# NVME.net
KiCad netlist of a schematic drawn in Altium Designer
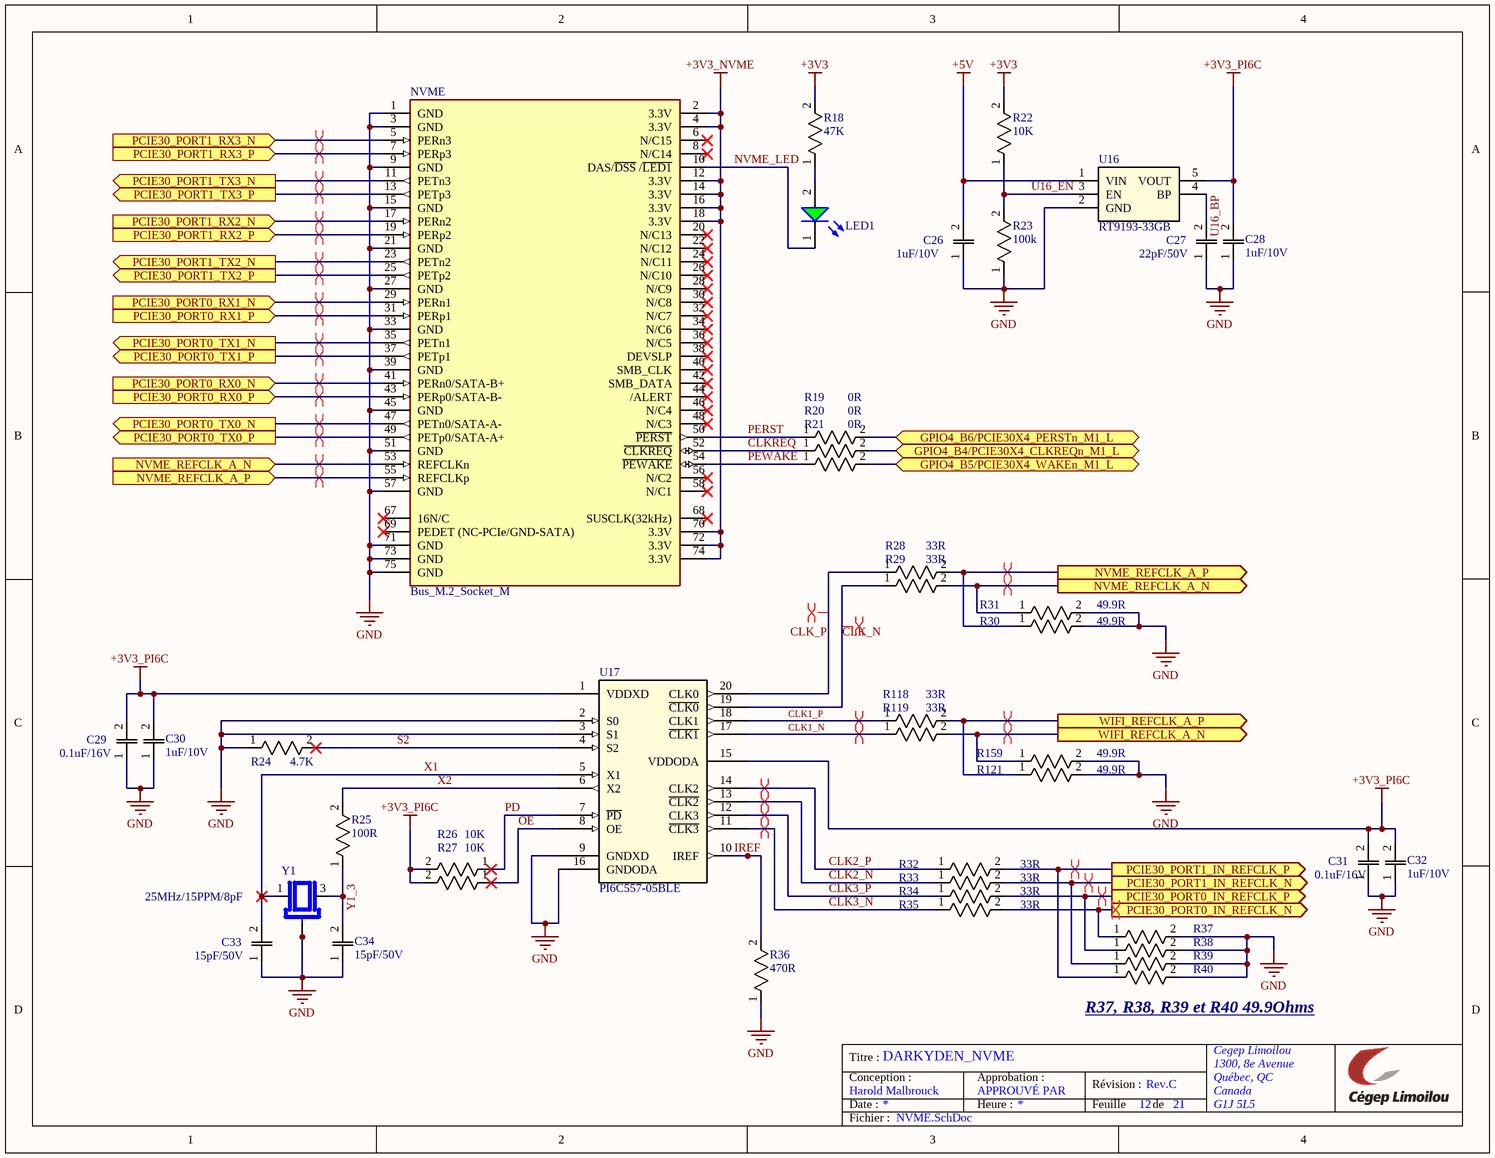
[diagram p0: NVME.SchDoc]

(export (version "E")
  (design (tool "Eeschema 10.0.6"))
  (components
    (comp (ref "C26")
      (value "1uF/10V")
      (footprint "C0805")
      (description "Multilayer Ceramic Capacitors MLCC - SMD/SMT 10V 1uF X7R 0805 10%")
      (fields
        (field (name "MANUFACTURER") "KEMET")
        (field (name "MANUFACTURER PART NUMBER") "C0805C105K3RACTU")
      )
      (libsource (lib "DARKYDEN") (part "C0805C105K8RACTU"))
    )
    (comp (ref "C27")
      (value "22pF/50V")
      (footprint "C0805")
      (description "Cap Ceramic 22pF 50V X7R 5% Pad SMD 0805 125°C T/R")
      (fields
        (field (name "MANUFACTURER") "KEMET")
        (field (name "MANUFACTURER PART NUMBER") "C0805C220J5RACTU")
      )
      (libsource (lib "DARKYDEN") (part "C0805C220J5RACTU"))
    )
    (comp (ref "C28")
      (value "1uF/10V")
      (footprint "C0805")
      (description "Multilayer Ceramic Capacitors MLCC - SMD/SMT 10V 1uF X7R 0805 10%")
      (fields
        (field (name "MANUFACTURER") "KEMET")
        (field (name "MANUFACTURER PART NUMBER") "C0805C105K3RACTU")
      )
      (libsource (lib "DARKYDEN") (part "C0805C105K8RACTU"))
    )
    (comp (ref "C29")
      (value "0.1uF/16V")
      (footprint "C0805")
      (description "0.1uF/16V ±10% X7R 0805 (2012METRIC) Ceramic Capacitor SMD Auto X7R")
      (fields
        (field (name "MANUFACTURER") "KEMET")
        (field (name "MANUFACTURER PART NUMBER") "C0805C104K5RACTU")
      )
      (libsource (lib "DARKYDEN") (part "C0805C104K4RACAUTO"))
    )
    (comp (ref "C30")
      (value "1uF/10V")
      (footprint "C0805")
      (description "Multilayer Ceramic Capacitors MLCC - SMD/SMT 10V 1uF X7R 0805 10%")
      (fields
        (field (name "MANUFACTURER") "KEMET")
        (field (name "MANUFACTURER PART NUMBER") "C0805C105K3RACTU")
      )
      (libsource (lib "DARKYDEN") (part "C0805C105K8RACTU"))
    )
    (comp (ref "C31")
      (value "0.1uF/16V")
      (footprint "C0805")
      (description "0.1uF/16V ±10% X7R 0805 (2012METRIC) Ceramic Capacitor SMD Auto X7R")
      (fields
        (field (name "MANUFACTURER") "KEMET")
        (field (name "MANUFACTURER PART NUMBER") "C0805C104K5RACTU")
      )
      (libsource (lib "DARKYDEN") (part "C0805C104K4RACAUTO"))
    )
    (comp (ref "C32")
      (value "1uF/10V")
      (footprint "C0805")
      (description "Multilayer Ceramic Capacitors MLCC - SMD/SMT 10V 1uF X7R 0805 10%")
      (fields
        (field (name "MANUFACTURER") "KEMET")
        (field (name "MANUFACTURER PART NUMBER") "C0805C105K3RACTU")
      )
      (libsource (lib "DARKYDEN") (part "C0805C105K8RACTU"))
    )
    (comp (ref "C33")
      (value "15pF/50V")
      (footprint "C0805")
      (description "Multilayer Ceramic Capacitors MLCC - SMD/SMT 50V 15pF X7R 0805 10% AEC-Q200")
      (fields
        (field (name "MANUFACTURER") "KEMET")
        (field (name "MANUFACTURER PART NUMBER") "C0805C150K5RACAUTO")
      )
      (libsource (lib "DARKYDEN") (part "C0805C150K5RACAUTO"))
    )
    (comp (ref "C34")
      (value "15pF/50V")
      (footprint "C0805")
      (description "Multilayer Ceramic Capacitors MLCC - SMD/SMT 50V 15pF X7R 0805 10% AEC-Q200")
      (fields
        (field (name "MANUFACTURER") "KEMET")
        (field (name "MANUFACTURER PART NUMBER") "C0805C150K5RACAUTO")
      )
      (libsource (lib "DARKYDEN") (part "C0805C150K5RACAUTO"))
    )
    (comp (ref "LED1")
      (value "Green, 3.2V, 140°")
      (footprint "WL-SMCD_0603")
      (description "WL-SMCD Mono-color Chip LED Diffused, SMT, size 0603, Green, 3.2V, 140°")
      (fields
        (field (name "MANUFACTURER PART NUMBER") "150060GS55040")
        (field (name "MANUFACTURER") "Wurth Elektronik")
      )
      (libsource (lib "0603_LED") (part "GREEN"))
    )
    (comp (ref "NVME")
      (value "Bus_M.2_Socket_M")
      (footprint "AMPHENOL_MDT420M03001")
      (fields
        (field (name "MF") "Amphenol Commercial")
        (field (name "MANUFACTURER PART NUMBER") "MDT420M03001")
      )
      (libsource (lib "Bus_M.2_Socket_M") (part "Bus_M.2_Socket_M"))
    )
    (comp (ref "R18")
      (value "47K")
      (footprint "RESC1608X55N")
      (description "47K Ohm 5% 1/10W 0603 200ppm/C Molded SMD Punched Carrier T/R")
      (fields
        (field (name "MANUFACTURER") "Panasonic")
        (field (name "MANUFACTURER PART NUMBER") "ERJ-3GEYJ473V")
      )
      (libsource (lib "DARKYDEN") (part "ERJ-3GEYJ473V"))
    )
    (comp (ref "R19")
      (value "0R")
      (footprint "SamacSys:RESC1608X55N")
      (description "Zero Ohm Resistor, Jumper, 0603 [1608 Metric], Thick Film, 100 mW, 1 A, Surface Mount")
      (fields
        (field (name "MOUSER PART NUMBER") "667-ERJ-3GEY0R00V")
        (field (name "ARROW PART NUMBER") "ERJ-3GEY0R00V")
      )
      (libsource (lib "DARKYDEN") (part "ERJ-3GEY0R00V"))
    )
    (comp (ref "R20")
      (value "0R")
      (footprint "SamacSys:RESC1608X55N")
      (description "Zero Ohm Resistor, Jumper, 0603 [1608 Metric], Thick Film, 100 mW, 1 A, Surface Mount")
      (fields
        (field (name "MOUSER PART NUMBER") "667-ERJ-3GEY0R00V")
        (field (name "ARROW PART NUMBER") "ERJ-3GEY0R00V")
      )
      (libsource (lib "DARKYDEN") (part "ERJ-3GEY0R00V"))
    )
    (comp (ref "R21")
      (value "0R")
      (footprint "SamacSys:RESC1608X55N")
      (description "Zero Ohm Resistor, Jumper, 0603 [1608 Metric], Thick Film, 100 mW, 1 A, Surface Mount")
      (fields
        (field (name "MOUSER PART NUMBER") "667-ERJ-3GEY0R00V")
        (field (name "ARROW PART NUMBER") "ERJ-3GEY0R00V")
      )
      (libsource (lib "DARKYDEN") (part "ERJ-3GEY0R00V"))
    )
    (comp (ref "R22")
      (value "10K")
      (footprint "SamacSys:RESC1608X55N")
      (description "10K Ohm 5% Res Thick Film 0603  0.1W(1/10W) ±200ppm/C Pad SMD Automotive T/R")
      (fields
        (field (name "MOUSER PART NUMBER") "667-ERJ-3GEYJ103V")
        (field (name "ARROW PART NUMBER") "ERJ-3GEYJ103V")
      )
      (libsource (lib "DARKYDEN") (part "ERJ-3GEYJ103V"))
    )
    (comp (ref "R23")
      (value "100k")
      (footprint "SamacSys:RESC1608X55N")
      (description "100K Ohm 5%  Res Thick Film 0603 1/10W +/-200ppm/ßC Molded SMD Punched Carrier T/R")
      (fields
        (field (name "MOUSER PART NUMBER") "667-ERJ-3GEYJ104V")
        (field (name "ARROW PART NUMBER") "ERJ-3GEYJ104V")
      )
      (libsource (lib "DARKYDEN") (part "ERJ-3GEYJ104V"))
    )
    (comp (ref "R24")
      (value "4.7K")
      (footprint "RESC1608X55N")
      (description "4.7K Ohm 0.1% 0.1W 0603 ±25ppm/°C Molded SMD Punched Carrier T/R")
      (fields
        (field (name "MANUFACTURER") "Panasonic")
        (field (name "MANUFACTURER PART NUMBER") "ERA-3AEB472V")
      )
      (libsource (lib "DARKYDEN") (part "ERA-3AEB472V"))
    )
    (comp (ref "R25")
      (value "100R")
      (footprint "SamacSys:RESC1608X55N")
      (description "100 Ohm 1% 1/10W 0603 ±100ppm/°C Molded SMD Punched Carrier T/R")
      (fields
        (field (name "MOUSER PART NUMBER") "667-ERJ-3EKF1000V")
        (field (name "ARROW PART NUMBER") "ERJ-3EKF1000V")
      )
      (libsource (lib "DARKYDEN") (part "ERJ-3EKF1000V"))
    )
    (comp (ref "R26")
      (value "10K")
      (footprint "SamacSys:RESC1608X55N")
      (description "10K Ohm 5% Res Thick Film 0603  0.1W(1/10W) ±200ppm/C Pad SMD Automotive T/R")
      (fields
        (field (name "MOUSER PART NUMBER") "667-ERJ-3GEYJ103V")
        (field (name "ARROW PART NUMBER") "ERJ-3GEYJ103V")
      )
      (libsource (lib "DARKYDEN") (part "ERJ-3GEYJ103V"))
    )
    (comp (ref "R27")
      (value "10K")
      (footprint "SamacSys:RESC1608X55N")
      (description "10K Ohm 5% Res Thick Film 0603  0.1W(1/10W) ±200ppm/C Pad SMD Automotive T/R")
      (fields
        (field (name "MOUSER PART NUMBER") "667-ERJ-3GEYJ103V")
        (field (name "ARROW PART NUMBER") "ERJ-3GEYJ103V")
      )
      (libsource (lib "DARKYDEN") (part "ERJ-3GEYJ103V"))
    )
    (comp (ref "R28")
      (value "33R")
      (footprint "RESC1608X55N")
      (description "33 Ohm 1% 0.1W 0603 ±100ppm/°C Molded SMD Punched Carrier T/R")
      (fields
        (field (name "MANUFACTURER") "Panasonic")
        (field (name "MANUFACTURER PART NUMBER") "ERJ-3EKF33R0V")
      )
      (libsource (lib "DARKYDEN") (part "ERJ-3EKF33R0V"))
    )
    (comp (ref "R29")
      (value "33R")
      (footprint "RESC1608X55N")
      (description "33 Ohm 1% 0.1W 0603 ±100ppm/°C Molded SMD Punched Carrier T/R")
      (fields
        (field (name "MANUFACTURER") "Panasonic")
        (field (name "MANUFACTURER PART NUMBER") "ERJ-3EKF33R0V")
      )
      (libsource (lib "DARKYDEN") (part "ERJ-3EKF33R0V"))
    )
    (comp (ref "R30")
      (value "49.9R")
      (footprint "RESC1608X55N")
      (description "100Mw Thick Film Resistors 100Ppm/ 1% 49.9 0603 Chip Resistor Surface Mount Rohs")
      (fields
        (field (name "MANUFACTURER") "Panasonic")
        (field (name "MANUFACTURER PART NUMBER") "ERJ-3EKF49R9V")
      )
      (libsource (lib "DARKYDEN") (part "ERJ-3EKF49R9V"))
    )
    (comp (ref "R31")
      (value "49.9R")
      (footprint "RESC1608X55N")
      (description "100Mw Thick Film Resistors 100Ppm/ 1% 49.9 0603 Chip Resistor Surface Mount Rohs")
      (fields
        (field (name "MANUFACTURER") "Panasonic")
        (field (name "MANUFACTURER PART NUMBER") "ERJ-3EKF49R9V")
      )
      (libsource (lib "DARKYDEN") (part "ERJ-3EKF49R9V"))
    )
    (comp (ref "R32")
      (value "33R")
      (footprint "RESC1608X55N")
      (description "33 Ohm 1% 0.1W 0603 ±100ppm/°C Molded SMD Punched Carrier T/R")
      (fields
        (field (name "MANUFACTURER") "Panasonic")
        (field (name "MANUFACTURER PART NUMBER") "ERJ-3EKF33R0V")
      )
      (libsource (lib "DARKYDEN") (part "ERJ-3EKF33R0V"))
    )
    (comp (ref "R33")
      (value "33R")
      (footprint "RESC1608X55N")
      (description "33 Ohm 1% 0.1W 0603 ±100ppm/°C Molded SMD Punched Carrier T/R")
      (fields
        (field (name "MANUFACTURER") "Panasonic")
        (field (name "MANUFACTURER PART NUMBER") "ERJ-3EKF33R0V")
      )
      (libsource (lib "DARKYDEN") (part "ERJ-3EKF33R0V"))
    )
    (comp (ref "R34")
      (value "33R")
      (footprint "RESC1608X55N")
      (description "33 Ohm 1% 0.1W 0603 ±100ppm/°C Molded SMD Punched Carrier T/R")
      (fields
        (field (name "MANUFACTURER") "Panasonic")
        (field (name "MANUFACTURER PART NUMBER") "ERJ-3EKF33R0V")
      )
      (libsource (lib "DARKYDEN") (part "ERJ-3EKF33R0V"))
    )
    (comp (ref "R35")
      (value "33R")
      (footprint "RESC1608X55N")
      (description "33 Ohm 1% 0.1W 0603 ±100ppm/°C Molded SMD Punched Carrier T/R")
      (fields
        (field (name "MANUFACTURER") "Panasonic")
        (field (name "MANUFACTURER PART NUMBER") "ERJ-3EKF33R0V")
      )
      (libsource (lib "DARKYDEN") (part "ERJ-3EKF33R0V"))
    )
    (comp (ref "R36")
      (value "470R")
      (footprint "RESC1608X55N")
      (description "470 Ohm 5% 1/10W 0603 +/-200ppm/ßC Molded SMD Punched Carrier T/R")
      (fields
        (field (name "MANUFACTURER") "Panasonic")
        (field (name "MANUFACTURER PART NUMBER") "ERJ-3GEYJ471V")
      )
      (libsource (lib "DARKYDEN") (part "ERJ-3GEYJ471V"))
    )
    (comp (ref "R37")
      (value "49.9R")
      (footprint "RESC1608X55N")
      (description "100Mw Thick Film Resistors 100Ppm/ 1% 49.9 0603 Chip Resistor Surface Mount Rohs")
      (fields
        (field (name "MANUFACTURER") "Panasonic")
        (field (name "MANUFACTURER PART NUMBER") "ERJ-3EKF49R9V")
      )
      (libsource (lib "DARKYDEN") (part "ERJ-3EKF49R9V"))
    )
    (comp (ref "R38")
      (value "49.9R")
      (footprint "RESC1608X55N")
      (description "100Mw Thick Film Resistors 100Ppm/ 1% 49.9 0603 Chip Resistor Surface Mount Rohs")
      (fields
        (field (name "MANUFACTURER") "Panasonic")
        (field (name "MANUFACTURER PART NUMBER") "ERJ-3EKF49R9V")
      )
      (libsource (lib "DARKYDEN") (part "ERJ-3EKF49R9V"))
    )
    (comp (ref "R39")
      (value "49.9R")
      (footprint "RESC1608X55N")
      (description "100Mw Thick Film Resistors 100Ppm/ 1% 49.9 0603 Chip Resistor Surface Mount Rohs")
      (fields
        (field (name "MANUFACTURER") "Panasonic")
        (field (name "MANUFACTURER PART NUMBER") "ERJ-3EKF49R9V")
      )
      (libsource (lib "DARKYDEN") (part "ERJ-3EKF49R9V"))
    )
    (comp (ref "R40")
      (value "49.9R")
      (footprint "RESC1608X55N")
      (description "100Mw Thick Film Resistors 100Ppm/ 1% 49.9 0603 Chip Resistor Surface Mount Rohs")
      (fields
        (field (name "MANUFACTURER") "Panasonic")
        (field (name "MANUFACTURER PART NUMBER") "ERJ-3EKF49R9V")
      )
      (libsource (lib "DARKYDEN") (part "ERJ-3EKF49R9V"))
    )
    (comp (ref "R118")
      (value "33R")
      (footprint "RESC1608X55N")
      (description "33 Ohm 1% 0.1W 0603 ±100ppm/°C Molded SMD Punched Carrier T/R")
      (fields
        (field (name "MANUFACTURER") "Panasonic")
        (field (name "MANUFACTURER PART NUMBER") "ERJ-3EKF33R0V")
      )
      (libsource (lib "DARKYDEN") (part "ERJ-3EKF33R0V"))
    )
    (comp (ref "R119")
      (value "33R")
      (footprint "RESC1608X55N")
      (description "33 Ohm 1% 0.1W 0603 ±100ppm/°C Molded SMD Punched Carrier T/R")
      (fields
        (field (name "MANUFACTURER") "Panasonic")
        (field (name "MANUFACTURER PART NUMBER") "ERJ-3EKF33R0V")
      )
      (libsource (lib "DARKYDEN") (part "ERJ-3EKF33R0V"))
    )
    (comp (ref "R121")
      (value "49.9R")
      (footprint "RESC1608X55N")
      (description "100Mw Thick Film Resistors 100Ppm/ 1% 49.9 0603 Chip Resistor Surface Mount Rohs")
      (fields
        (field (name "MANUFACTURER") "Panasonic")
        (field (name "MANUFACTURER PART NUMBER") "ERJ-3EKF49R9V")
      )
      (libsource (lib "DARKYDEN") (part "ERJ-3EKF49R9V"))
    )
    (comp (ref "R159")
      (value "49.9R")
      (footprint "RESC1608X55N")
      (description "100Mw Thick Film Resistors 100Ppm/ 1% 49.9 0603 Chip Resistor Surface Mount Rohs")
      (fields
        (field (name "MANUFACTURER") "Panasonic")
        (field (name "MANUFACTURER PART NUMBER") "ERJ-3EKF49R9V")
      )
      (libsource (lib "DARKYDEN") (part "ERJ-3EKF49R9V"))
    )
    (comp (ref "U16")
      (value "RT9193-33GB")
      (footprint "SOT-23-5_RIT")
      (description "RT9193 Series 300 mA 3.3 V Ultra-Low Noise Ultra-Fast CMOS LDO Regulator-SC-70-5")
      (fields (field (name "MANUFACTURER") "Richtek"))
      (libsource (lib "DARKYDEN") (part "RT9193-33GB"))
    )
    (comp (ref "U17")
      (value "PI6C557-05BLE")
      (footprint "L20_PER-M")
      (description "Clock Generators & Support Products PCI express Gen 2 4 output clock gen")
      (fields (field (name "MANUFACTURER") "Diodes"))
      (libsource (lib "PI6C557-05BLE") (part "PI6C557-05BLE"))
    )
    (comp (ref "Y1")
      (value "25MHz/15PPM/8pF")
      (footprint "XTAL_ECS-250-8-37B2-RWY-TR")
      (description "Crystal 25MHz ±15ppm (Tol) ±15ppm (Stability) 8pF FUND 50Ohm 4-Pin Mini-CSMD T/R")
      (fields (field (name "MF") "{'manufacturer': u'ECS Inc.'}") (field (name "MP") "ECS-250-8-37B2-RWY-TR"))
      (libsource (lib "ECS-250-8-37B2-RWY-TR") (part "ECS-250-8-37B2-RWY-TR"))
    )
  )
  (nets
    (net (code "1") (name "+3V3") (class "Default")
      (node (ref "R18") (pin "2") (pinfunction "2_2") (pintype "passive"))
      (node (ref "R22") (pin "2") (pinfunction "2_2") (pintype "passive"))
    )
    (net (code "2") (name "+3V3_NVME") (class "Default")
      (node (ref "NVME") (pin "12") (pinfunction "3.3V_12") (pintype "power_in"))
      (node (ref "NVME") (pin "14") (pinfunction "3.3V_14") (pintype "power_in"))
      (node (ref "NVME") (pin "16") (pinfunction "3.3V_16") (pintype "power_in"))
      (node (ref "NVME") (pin "18") (pinfunction "3.3V_18") (pintype "power_in"))
      (node (ref "NVME") (pin "2") (pinfunction "3.3V_2") (pintype "power_in"))
      (node (ref "NVME") (pin "4") (pinfunction "3.3V_4") (pintype "power_in"))
      (node (ref "NVME") (pin "70") (pinfunction "3.3V_70") (pintype "power_in"))
      (node (ref "NVME") (pin "72") (pinfunction "3.3V_72") (pintype "power_in"))
      (node (ref "NVME") (pin "74") (pinfunction "3.3V_74") (pintype "power_in"))
    )
    (net (code "3") (name "+3V3_PI6C") (class "Default")
      (node (ref "C28") (pin "2") (pinfunction "2_2") (pintype "passive"))
      (node (ref "C29") (pin "2") (pinfunction "2_2") (pintype "passive"))
      (node (ref "C30") (pin "2") (pinfunction "2_2") (pintype "passive"))
      (node (ref "C31") (pin "2") (pinfunction "2_2") (pintype "passive"))
      (node (ref "C32") (pin "2") (pinfunction "2_2") (pintype "passive"))
      (node (ref "R26") (pin "2") (pinfunction "2_2") (pintype "passive"))
      (node (ref "R27") (pin "2") (pinfunction "2_2") (pintype "passive"))
      (node (ref "U16") (pin "5") (pinfunction "VOUT_5") (pintype "power_in"))
      (node (ref "U17") (pin "1") (pinfunction "VDDXD_1") (pintype "power_in"))
      (node (ref "U17") (pin "15") (pinfunction "VDDODA_15") (pintype "power_in"))
    )
    (net (code "4") (name "+5V") (class "Default")
      (node (ref "C26") (pin "2") (pinfunction "2_2") (pintype "passive"))
      (node (ref "U16") (pin "1") (pinfunction "VIN_1") (pintype "power_in"))
    )
    (net (code "5") (name "/CLK1_N") (class "Default")
      (node (ref "R119") (pin "1") (pinfunction "1_1") (pintype "passive"))
      (node (ref "U17") (pin "17") (pinfunction "~{CLK1}_17") (pintype "output"))
    )
    (net (code "6") (name "/CLK1_P") (class "Default")
      (node (ref "R118") (pin "1") (pinfunction "1_1") (pintype "passive"))
      (node (ref "U17") (pin "18") (pinfunction "CLK1_18") (pintype "output"))
    )
    (net (code "7") (name "/CLK2_N") (class "Default")
      (node (ref "R33") (pin "1") (pinfunction "1_1") (pintype "passive"))
      (node (ref "U17") (pin "13") (pinfunction "~{CLK2}_13") (pintype "output"))
    )
    (net (code "8") (name "/CLK2_P") (class "Default")
      (node (ref "R32") (pin "1") (pinfunction "1_1") (pintype "passive"))
      (node (ref "U17") (pin "14") (pinfunction "CLK2_14") (pintype "output"))
    )
    (net (code "9") (name "/CLK3_N") (class "Default")
      (node (ref "R35") (pin "1") (pinfunction "1_1") (pintype "passive"))
      (node (ref "U17") (pin "11") (pinfunction "~{CLK3}_11") (pintype "output"))
    )
    (net (code "10") (name "/CLK3_P") (class "Default")
      (node (ref "R34") (pin "1") (pinfunction "1_1") (pintype "passive"))
      (node (ref "U17") (pin "12") (pinfunction "CLK3_12") (pintype "output"))
    )
    (net (code "11") (name "/CLKREQ") (class "Default")
      (node (ref "NVME") (pin "52") (pinfunction "~{CLKREQ}_52") (pintype "bidirectional"))
      (node (ref "R20") (pin "1") (pinfunction "1_1") (pintype "passive"))
    )
    (net (code "12") (name "/CLK_N") (class "Default")
      (node (ref "R29") (pin "1") (pinfunction "1_1") (pintype "passive"))
      (node (ref "U17") (pin "19") (pinfunction "~{CLK0}_19") (pintype "output"))
    )
    (net (code "13") (name "/CLK_P") (class "Default")
      (node (ref "R28") (pin "1") (pinfunction "1_1") (pintype "passive"))
      (node (ref "U17") (pin "20") (pinfunction "CLK0_20") (pintype "output"))
    )
    (net (code "14") (name "/GPIO4_B4{slash}PCIE30X4_CLKREQn_M1_L") (class "Default")
      (node (ref "R20") (pin "2") (pinfunction "2_2") (pintype "passive"))
    )
    (net (code "15") (name "/GPIO4_B5{slash}PCIE30X4_WAKEn_M1_L") (class "Default")
      (node (ref "R21") (pin "2") (pinfunction "2_2") (pintype "passive"))
    )
    (net (code "16") (name "/GPIO4_B6{slash}PCIE30X4_PERSTn_M1_L") (class "Default")
      (node (ref "R19") (pin "2") (pinfunction "2_2") (pintype "passive"))
    )
    (net (code "17") (name "/IREF") (class "Default")
      (node (ref "R36") (pin "2") (pinfunction "2_2") (pintype "passive"))
      (node (ref "U17") (pin "10") (pinfunction "IREF_10") (pintype "output"))
    )
    (net (code "18") (name "/NVME_LED") (class "Default")
      (node (ref "LED1") (pin "1") (pinfunction "K_1") (pintype "passive"))
      (node (ref "NVME") (pin "10") (pinfunction "DAS/~{DSS}_/~{LED1}_10") (pintype "passive"))
    )
    (net (code "19") (name "/NVME_REFCLK_A_N") (class "Default")
      (node (ref "NVME") (pin "53") (pinfunction "REFCLKn_53") (pintype "input"))
      (node (ref "R29") (pin "2") (pinfunction "2_2") (pintype "passive"))
      (node (ref "R31") (pin "1") (pinfunction "1_1") (pintype "passive"))
    )
    (net (code "20") (name "/NVME_REFCLK_A_P") (class "Default")
      (node (ref "NVME") (pin "55") (pinfunction "REFCLKp_55") (pintype "input"))
      (node (ref "R28") (pin "2") (pinfunction "2_2") (pintype "passive"))
      (node (ref "R30") (pin "1") (pinfunction "1_1") (pintype "passive"))
    )
    (net (code "21") (name "/OE") (class "Default")
      (node (ref "R27") (pin "1") (pinfunction "1_1") (pintype "passive"))
      (node (ref "U17") (pin "8") (pinfunction "OE_8") (pintype "input"))
    )
    (net (code "22") (name "/PCIE30_PORT0_IN_REFCLK_N") (class "Default")
      (node (ref "R35") (pin "2") (pinfunction "2_2") (pintype "passive"))
      (node (ref "R37") (pin "1") (pinfunction "1_1") (pintype "passive"))
    )
    (net (code "23") (name "/PCIE30_PORT0_IN_REFCLK_P") (class "Default")
      (node (ref "R34") (pin "2") (pinfunction "2_2") (pintype "passive"))
      (node (ref "R38") (pin "1") (pinfunction "1_1") (pintype "passive"))
    )
    (net (code "24") (name "/PCIE30_PORT0_RX0_N") (class "Default")
      (node (ref "NVME") (pin "41") (pinfunction "PERn0/SATA-B+_41") (pintype "input"))
    )
    (net (code "25") (name "/PCIE30_PORT0_RX0_P") (class "Default")
      (node (ref "NVME") (pin "43") (pinfunction "PERp0/SATA-B-_43") (pintype "input"))
    )
    (net (code "26") (name "/PCIE30_PORT0_RX1_N") (class "Default")
      (node (ref "NVME") (pin "29") (pinfunction "PERn1_29") (pintype "input"))
    )
    (net (code "27") (name "/PCIE30_PORT0_RX1_P") (class "Default")
      (node (ref "NVME") (pin "31") (pinfunction "PERp1_31") (pintype "input"))
    )
    (net (code "28") (name "/PCIE30_PORT0_TX0_N") (class "Default")
      (node (ref "NVME") (pin "47") (pinfunction "PETn0/SATA-A-_47") (pintype "output"))
    )
    (net (code "29") (name "/PCIE30_PORT0_TX0_P") (class "Default")
      (node (ref "NVME") (pin "49") (pinfunction "PETp0/SATA-A+_49") (pintype "output"))
    )
    (net (code "30") (name "/PCIE30_PORT0_TX1_N") (class "Default")
      (node (ref "NVME") (pin "35") (pinfunction "PETn1_35") (pintype "output"))
    )
    (net (code "31") (name "/PCIE30_PORT0_TX1_P") (class "Default")
      (node (ref "NVME") (pin "37") (pinfunction "PETp1_37") (pintype "output"))
    )
    (net (code "32") (name "/PCIE30_PORT1_IN_REFCLK_N") (class "Default")
      (node (ref "R33") (pin "2") (pinfunction "2_2") (pintype "passive"))
      (node (ref "R39") (pin "1") (pinfunction "1_1") (pintype "passive"))
    )
    (net (code "33") (name "/PCIE30_PORT1_IN_REFCLK_P") (class "Default")
      (node (ref "R32") (pin "2") (pinfunction "2_2") (pintype "passive"))
      (node (ref "R40") (pin "1") (pinfunction "1_1") (pintype "passive"))
    )
    (net (code "34") (name "/PCIE30_PORT1_RX2_N") (class "Default")
      (node (ref "NVME") (pin "17") (pinfunction "PERn2_17") (pintype "input"))
    )
    (net (code "35") (name "/PCIE30_PORT1_RX2_P") (class "Default")
      (node (ref "NVME") (pin "19") (pinfunction "PERp2_19") (pintype "input"))
    )
    (net (code "36") (name "/PCIE30_PORT1_RX3_N") (class "Default")
      (node (ref "NVME") (pin "5") (pinfunction "PERn3_5") (pintype "input"))
    )
    (net (code "37") (name "/PCIE30_PORT1_RX3_P") (class "Default")
      (node (ref "NVME") (pin "7") (pinfunction "PERp3_7") (pintype "input"))
    )
    (net (code "38") (name "/PCIE30_PORT1_TX2_N") (class "Default")
      (node (ref "NVME") (pin "23") (pinfunction "PETn2_23") (pintype "output"))
    )
    (net (code "39") (name "/PCIE30_PORT1_TX2_P") (class "Default")
      (node (ref "NVME") (pin "25") (pinfunction "PETp2_25") (pintype "output"))
    )
    (net (code "40") (name "/PCIE30_PORT1_TX3_N") (class "Default")
      (node (ref "NVME") (pin "11") (pinfunction "PETn3_11") (pintype "output"))
    )
    (net (code "41") (name "/PCIE30_PORT1_TX3_P") (class "Default")
      (node (ref "NVME") (pin "13") (pinfunction "PETp3_13") (pintype "output"))
    )
    (net (code "42") (name "/PD") (class "Default")
      (node (ref "R26") (pin "1") (pinfunction "1_1") (pintype "passive"))
      (node (ref "U17") (pin "7") (pinfunction "~{PD}_7") (pintype "input"))
    )
    (net (code "43") (name "/PERST") (class "Default")
      (node (ref "NVME") (pin "50") (pinfunction "~{PERST}_50") (pintype "output"))
      (node (ref "R19") (pin "1") (pinfunction "1_1") (pintype "passive"))
    )
    (net (code "44") (name "/PEWAKE") (class "Default")
      (node (ref "NVME") (pin "54") (pinfunction "~{PEWAKE}_54") (pintype "bidirectional"))
      (node (ref "R21") (pin "1") (pinfunction "1_1") (pintype "passive"))
    )
    (net (code "45") (name "/S2") (class "Default")
      (node (ref "R24") (pin "2") (pinfunction "2_2") (pintype "passive"))
      (node (ref "U17") (pin "4") (pinfunction "S2_4") (pintype "input"))
    )
    (net (code "46") (name "/U16_BP") (class "Default")
      (node (ref "C27") (pin "2") (pinfunction "2_2") (pintype "passive"))
      (node (ref "U16") (pin "4") (pinfunction "BP_4") (pintype "passive"))
    )
    (net (code "47") (name "/U16_EN") (class "Default")
      (node (ref "R22") (pin "1") (pinfunction "1_1") (pintype "passive"))
      (node (ref "R23") (pin "2") (pinfunction "2_2") (pintype "passive"))
      (node (ref "U16") (pin "3") (pinfunction "EN_3") (pintype "passive"))
    )
    (net (code "48") (name "/WIFI_REFCLK_A_N") (class "Default")
      (node (ref "R119") (pin "2") (pinfunction "2_2") (pintype "passive"))
      (node (ref "R159") (pin "1") (pinfunction "1_1") (pintype "passive"))
    )
    (net (code "49") (name "/WIFI_REFCLK_A_P") (class "Default")
      (node (ref "R118") (pin "2") (pinfunction "2_2") (pintype "passive"))
      (node (ref "R121") (pin "1") (pinfunction "1_1") (pintype "passive"))
    )
    (net (code "50") (name "/X1") (class "Default")
      (node (ref "C33") (pin "2") (pinfunction "2_2") (pintype "passive"))
      (node (ref "U17") (pin "5") (pinfunction "X1_5") (pintype "input"))
      (node (ref "Y1") (pin "1") (pinfunction "IN/OUT_1") (pintype "passive"))
    )
    (net (code "51") (name "/X2") (class "Default")
      (node (ref "R25") (pin "2") (pinfunction "2_2") (pintype "passive"))
      (node (ref "U17") (pin "6") (pinfunction "X2_6") (pintype "output"))
    )
    (net (code "52") (name "/Y1_3") (class "Default")
      (node (ref "C34") (pin "2") (pinfunction "2_2") (pintype "passive"))
      (node (ref "R25") (pin "1") (pinfunction "1_1") (pintype "passive"))
      (node (ref "Y1") (pin "3") (pinfunction "OUT/IN_3") (pintype "passive"))
    )
    (net (code "53") (name "GND") (class "Default")
      (node (ref "C26") (pin "1") (pinfunction "1_1") (pintype "passive"))
      (node (ref "C27") (pin "1") (pinfunction "1_1") (pintype "passive"))
      (node (ref "C28") (pin "1") (pinfunction "1_1") (pintype "passive"))
      (node (ref "C29") (pin "1") (pinfunction "1_1") (pintype "passive"))
      (node (ref "C30") (pin "1") (pinfunction "1_1") (pintype "passive"))
      (node (ref "C31") (pin "1") (pinfunction "1_1") (pintype "passive"))
      (node (ref "C32") (pin "1") (pinfunction "1_1") (pintype "passive"))
      (node (ref "C33") (pin "1") (pinfunction "1_1") (pintype "passive"))
      (node (ref "C34") (pin "1") (pinfunction "1_1") (pintype "passive"))
      (node (ref "NVME") (pin "1") (pinfunction "GND_1") (pintype "passive"))
      (node (ref "NVME") (pin "15") (pinfunction "GND_15") (pintype "passive"))
      (node (ref "NVME") (pin "21") (pinfunction "GND_21") (pintype "passive"))
      (node (ref "NVME") (pin "27") (pinfunction "GND_27") (pintype "passive"))
      (node (ref "NVME") (pin "3") (pinfunction "GND_3") (pintype "passive"))
      (node (ref "NVME") (pin "33") (pinfunction "GND_33") (pintype "passive"))
      (node (ref "NVME") (pin "39") (pinfunction "GND_39") (pintype "passive"))
      (node (ref "NVME") (pin "45") (pinfunction "GND_45") (pintype "passive"))
      (node (ref "NVME") (pin "51") (pinfunction "GND_51") (pintype "passive"))
      (node (ref "NVME") (pin "57") (pinfunction "GND_57") (pintype "passive"))
      (node (ref "NVME") (pin "71") (pinfunction "GND_71") (pintype "passive"))
      (node (ref "NVME") (pin "73") (pinfunction "GND_73") (pintype "passive"))
      (node (ref "NVME") (pin "75") (pinfunction "GND_75") (pintype "passive"))
      (node (ref "NVME") (pin "9") (pinfunction "GND_9") (pintype "passive"))
      (node (ref "R121") (pin "2") (pinfunction "2_2") (pintype "passive"))
      (node (ref "R159") (pin "2") (pinfunction "2_2") (pintype "passive"))
      (node (ref "R23") (pin "1") (pinfunction "1_1") (pintype "passive"))
      (node (ref "R24") (pin "1") (pinfunction "1_1") (pintype "passive"))
      (node (ref "R30") (pin "2") (pinfunction "2_2") (pintype "passive"))
      (node (ref "R31") (pin "2") (pinfunction "2_2") (pintype "passive"))
      (node (ref "R36") (pin "1") (pinfunction "1_1") (pintype "passive"))
      (node (ref "R37") (pin "2") (pinfunction "2_2") (pintype "passive"))
      (node (ref "R38") (pin "2") (pinfunction "2_2") (pintype "passive"))
      (node (ref "R39") (pin "2") (pinfunction "2_2") (pintype "passive"))
      (node (ref "R40") (pin "2") (pinfunction "2_2") (pintype "passive"))
      (node (ref "U16") (pin "2") (pinfunction "GND_2") (pintype "passive"))
      (node (ref "U17") (pin "16") (pinfunction "GNDODA_16") (pintype "passive"))
      (node (ref "U17") (pin "2") (pinfunction "S0_2") (pintype "input"))
      (node (ref "U17") (pin "3") (pinfunction "S1_3") (pintype "input"))
      (node (ref "U17") (pin "9") (pinfunction "GNDXD_9") (pintype "passive"))
      (node (ref "Y1") (pin "2") (pinfunction "GND_2") (pintype "power_in"))
      (node (ref "Y1") (pin "4") (pinfunction "GND_4") (pintype "power_in"))
    )
    (net (code "54") (name "Net-(LED1-A)") (class "Default")
      (node (ref "LED1") (pin "2") (pinfunction "A_2") (pintype "passive"))
      (node (ref "R18") (pin "1") (pinfunction "1_1") (pintype "passive"))
    )
    (net (code "55") (name "unconnected-(NVME-16N{slash}C-Pad67)") (class "Default")
      (node (ref "NVME") (pin "67") (pinfunction "16N/C_67") (pintype "passive+no_connect"))
    )
    (net (code "56") (name "unconnected-(NVME-DEVSLP-Pad38)") (class "Default")
      (node (ref "NVME") (pin "38") (pinfunction "DEVSLP_38") (pintype "passive+no_connect"))
    )
    (net (code "57") (name "unconnected-(NVME-N{slash}C1-Pad58)") (class "Default")
      (node (ref "NVME") (pin "58") (pinfunction "N/C1_58") (pintype "passive+no_connect"))
    )
    (net (code "58") (name "unconnected-(NVME-N{slash}C2-Pad56)") (class "Default")
      (node (ref "NVME") (pin "56") (pinfunction "N/C2_56") (pintype "passive+no_connect"))
    )
    (net (code "59") (name "unconnected-(NVME-N{slash}C3-Pad48)") (class "Default")
      (node (ref "NVME") (pin "48") (pinfunction "N/C3_48") (pintype "passive+no_connect"))
    )
    (net (code "60") (name "unconnected-(NVME-N{slash}C4-Pad46)") (class "Default")
      (node (ref "NVME") (pin "46") (pinfunction "N/C4_46") (pintype "passive+no_connect"))
    )
    (net (code "61") (name "unconnected-(NVME-N{slash}C5-Pad36)") (class "Default")
      (node (ref "NVME") (pin "36") (pinfunction "N/C5_36") (pintype "passive+no_connect"))
    )
    (net (code "62") (name "unconnected-(NVME-N{slash}C6-Pad34)") (class "Default")
      (node (ref "NVME") (pin "34") (pinfunction "N/C6_34") (pintype "passive+no_connect"))
    )
    (net (code "63") (name "unconnected-(NVME-N{slash}C7-Pad32)") (class "Default")
      (node (ref "NVME") (pin "32") (pinfunction "N/C7_32") (pintype "passive+no_connect"))
    )
    (net (code "64") (name "unconnected-(NVME-N{slash}C8-Pad30)") (class "Default")
      (node (ref "NVME") (pin "30") (pinfunction "N/C8_30") (pintype "passive+no_connect"))
    )
    (net (code "65") (name "unconnected-(NVME-N{slash}C9-Pad28)") (class "Default")
      (node (ref "NVME") (pin "28") (pinfunction "N/C9_28") (pintype "passive+no_connect"))
    )
    (net (code "66") (name "unconnected-(NVME-N{slash}C10-Pad26)") (class "Default")
      (node (ref "NVME") (pin "26") (pinfunction "N/C10_26") (pintype "passive+no_connect"))
    )
    (net (code "67") (name "unconnected-(NVME-N{slash}C11-Pad24)") (class "Default")
      (node (ref "NVME") (pin "24") (pinfunction "N/C11_24") (pintype "passive+no_connect"))
    )
    (net (code "68") (name "unconnected-(NVME-N{slash}C12-Pad22)") (class "Default")
      (node (ref "NVME") (pin "22") (pinfunction "N/C12_22") (pintype "passive+no_connect"))
    )
    (net (code "69") (name "unconnected-(NVME-N{slash}C13-Pad20)") (class "Default")
      (node (ref "NVME") (pin "20") (pinfunction "N/C13_20") (pintype "passive+no_connect"))
    )
    (net (code "70") (name "unconnected-(NVME-N{slash}C14-Pad8)") (class "Default")
      (node (ref "NVME") (pin "8") (pinfunction "N/C14_8") (pintype "passive+no_connect"))
    )
    (net (code "71") (name "unconnected-(NVME-N{slash}C15-Pad6)") (class "Default")
      (node (ref "NVME") (pin "6") (pinfunction "N/C15_6") (pintype "passive+no_connect"))
    )
    (net (code "72") (name "unconnected-(NVME-PEDET_(NC-PCIe{slash}GND-SATA)-Pad69)") (class "Default")
      (node (ref "NVME") (pin "69") (pinfunction "PEDET_(NC-PCIe/GND-SATA)_69") (pintype "passive+no_connect"))
    )
    (net (code "73") (name "unconnected-(NVME-SMB_CLK-Pad40)") (class "Default")
      (node (ref "NVME") (pin "40") (pinfunction "SMB_CLK_40") (pintype "passive+no_connect"))
    )
    (net (code "74") (name "unconnected-(NVME-SMB_DATA-Pad42)") (class "Default")
      (node (ref "NVME") (pin "42") (pinfunction "SMB_DATA_42") (pintype "passive+no_connect"))
    )
    (net (code "75") (name "unconnected-(NVME-SUSCLK(32kHz)-Pad68)") (class "Default")
      (node (ref "NVME") (pin "68") (pinfunction "SUSCLK(32kHz)_68") (pintype "passive+no_connect"))
    )
    (net (code "76") (name "unconnected-(NVME-{slash}ALERT-Pad44)") (class "Default")
      (node (ref "NVME") (pin "44") (pinfunction "/ALERT_44") (pintype "passive+no_connect"))
    )
  )
)
